# v1_0.net
KiCad netlist of a schematic drawn in EasyEDA Pro
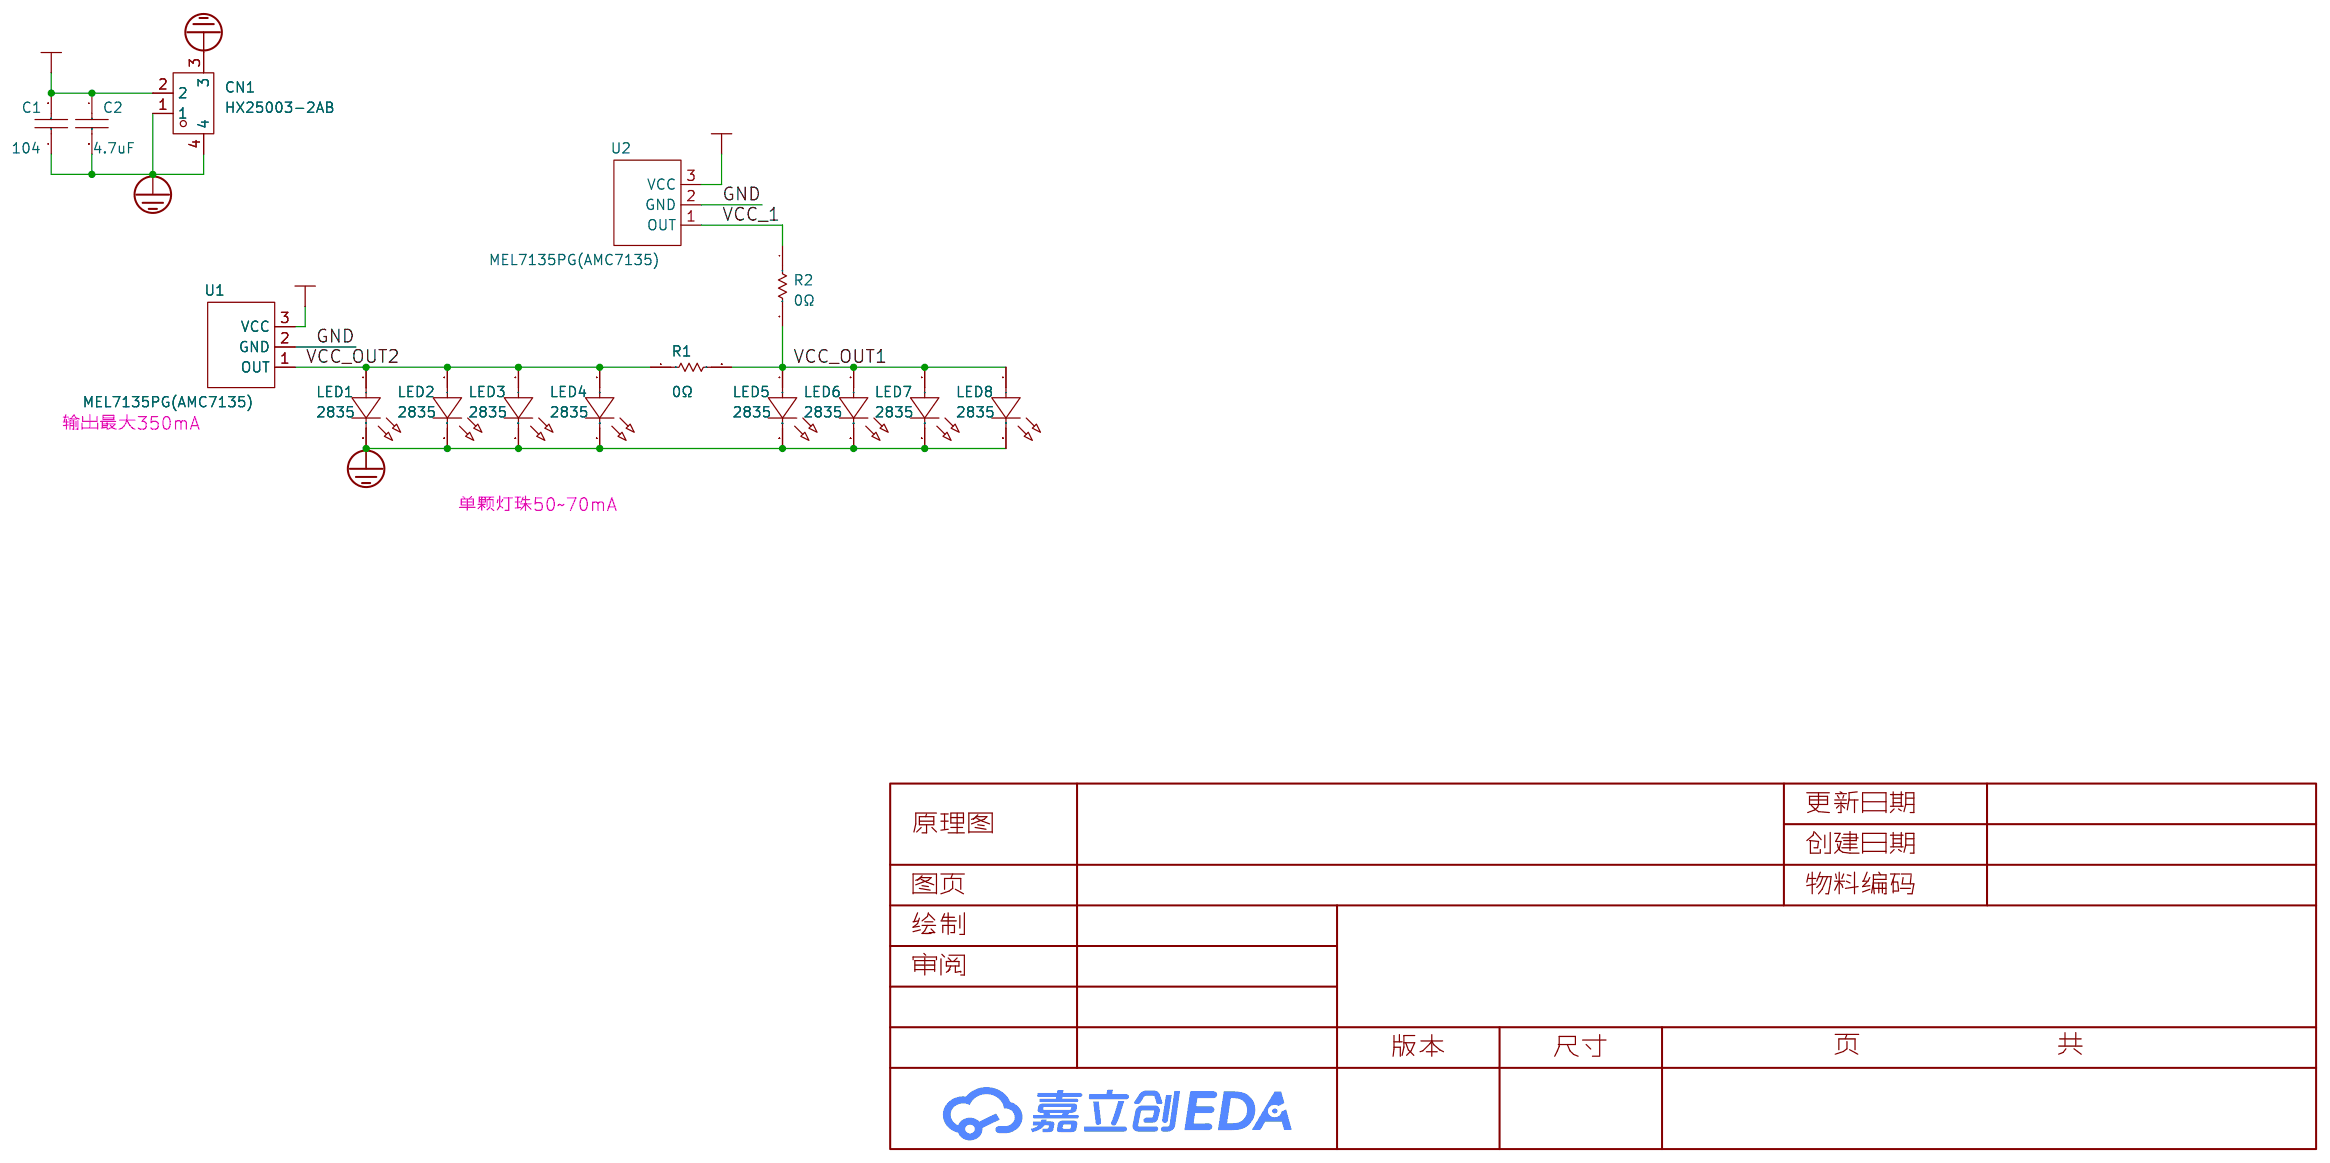
[diagram p0: schematic sheet]

(export (version "E")
  (design (tool "Eeschema 10.0.6"))
  (components
    (comp (ref "C1")
      (value "104")
      (footprint "easyedapro:0603C")
      (description "Capacitor (Semiconductor SIM Model)")
      (libsource (lib "easyedapro") (part "Cap Semi"))
    )
    (comp (ref "C2") (value "4.7uF") (libsource (lib "easyedapro") (part "CAP")))
    (comp (ref "CN1")
      (value "HX25003-2AB")
      (footprint "easyedapro:CONN-SMD_P2.50_HX25003-2AB")
      (fields (field (name "Manufacturer") "HX(红星)"))
      (libsource (lib "easyedapro") (part "HX25003-2AB"))
    )
    (comp (ref "LED1")
      (value "2835")
      (footprint "easyedapro:LED-SMD_L3.5-W2.8_2835")
      (libsource (lib "easyedapro") (part "2835"))
    )
    (comp (ref "LED2")
      (value "2835")
      (footprint "easyedapro:LED-SMD_L3.5-W2.8_2835")
      (libsource (lib "easyedapro") (part "2835"))
    )
    (comp (ref "LED3")
      (value "2835")
      (footprint "easyedapro:LED-SMD_L3.5-W2.8_2835")
      (libsource (lib "easyedapro") (part "2835"))
    )
    (comp (ref "LED4")
      (value "2835")
      (footprint "easyedapro:LED-SMD_L3.5-W2.8_2835")
      (libsource (lib "easyedapro") (part "2835"))
    )
    (comp (ref "LED5")
      (value "2835")
      (footprint "easyedapro:LED-SMD_L3.5-W2.8_2835")
      (libsource (lib "easyedapro") (part "2835"))
    )
    (comp (ref "LED6")
      (value "2835")
      (footprint "easyedapro:LED-SMD_L3.5-W2.8_2835")
      (libsource (lib "easyedapro") (part "2835"))
    )
    (comp (ref "LED7")
      (value "2835")
      (footprint "easyedapro:LED-SMD_L3.5-W2.8_2835")
      (libsource (lib "easyedapro") (part "2835"))
    )
    (comp (ref "LED8")
      (value "2835")
      (footprint "easyedapro:LED-SMD_L3.5-W2.8_2835")
      (libsource (lib "easyedapro") (part "2835"))
    )
    (comp (ref "R1")
      (value "0Ω")
      (footprint "easyedapro:10")
      (description "Resistor")
      (libsource (lib "easyedapro") (part "RES"))
    )
    (comp (ref "R2")
      (value "0Ω")
      (footprint "easyedapro:10")
      (description "Resistor")
      (libsource (lib "easyedapro") (part "RES"))
    )
    (comp (ref "U1")
      (value "MEL7135PG(AMC7135)")
      (footprint "easyedapro:SOT-89-3_L4.5-W2.5-P1.50-LS4.2-BR")
      (description "类型:-;工作电压(DC):2.7V~6V;开关频率:-;通道数:1;输出电压:-;输出电流:350mA;调光:-;拓扑结构:-;")
      (fields (field (name "Manufacturer") "MICRONE(南京微盟)"))
      (libsource (lib "easyedapro") (part "MEL7135PG"))
    )
    (comp (ref "U2")
      (value "MEL7135PG(AMC7135)")
      (footprint "easyedapro:SOT-89-3_L4.5-W2.5-P1.50-LS4.2-BR")
      (description "类型:-;工作电压(DC):2.7V~6V;开关频率:-;通道数:1;输出电压:-;输出电流:350mA;调光:-;拓扑结构:-;")
      (fields (field (name "Manufacturer") "MICRONE(南京微盟)"))
      (libsource (lib "easyedapro") (part "MEL7135PG"))
    )
  )
  (nets
    (net (code "1") (name "/VCC_1") (class "Default")
      (node (ref "R2") (pin "1") (pinfunction "1_1") (pintype "unspecified"))
      (node (ref "U2") (pin "1") (pinfunction "OUT_1") (pintype "unspecified"))
    )
    (net (code "2") (name "/VCC_OUT1") (class "Default")
      (node (ref "LED5") (pin "1") (pinfunction "A_1") (pintype "unspecified"))
      (node (ref "LED6") (pin "1") (pinfunction "A_1") (pintype "unspecified"))
      (node (ref "LED7") (pin "1") (pinfunction "A_1") (pintype "unspecified"))
      (node (ref "LED8") (pin "1") (pinfunction "A_1") (pintype "unspecified"))
      (node (ref "R1") (pin "2") (pinfunction "2_2") (pintype "unspecified"))
      (node (ref "R2") (pin "2") (pinfunction "2_2") (pintype "unspecified"))
    )
    (net (code "3") (name "/VCC_OUT2") (class "Default")
      (node (ref "LED1") (pin "1") (pinfunction "A_1") (pintype "unspecified"))
      (node (ref "LED2") (pin "1") (pinfunction "A_1") (pintype "unspecified"))
      (node (ref "LED3") (pin "1") (pinfunction "A_1") (pintype "unspecified"))
      (node (ref "LED4") (pin "1") (pinfunction "A_1") (pintype "unspecified"))
      (node (ref "R1") (pin "1") (pinfunction "1_1") (pintype "unspecified"))
      (node (ref "U1") (pin "1") (pinfunction "OUT_1") (pintype "unspecified"))
    )
    (net (code "4") (name "5V_VCC") (class "Default")
      (node (ref "C1") (pin "2") (pinfunction "2_2") (pintype "unspecified"))
      (node (ref "C2") (pin "1") (pinfunction "1_1") (pintype "input"))
      (node (ref "CN1") (pin "2") (pinfunction "2_2") (pintype "unspecified"))
      (node (ref "U1") (pin "3") (pinfunction "VCC_3") (pintype "unspecified"))
      (node (ref "U2") (pin "3") (pinfunction "VCC_3") (pintype "unspecified"))
    )
    (net (code "5") (name "GND") (class "Default")
      (node (ref "C1") (pin "1") (pinfunction "1_1") (pintype "unspecified"))
      (node (ref "C2") (pin "2") (pinfunction "2_2") (pintype "input"))
      (node (ref "CN1") (pin "1") (pinfunction "1_1") (pintype "unspecified"))
      (node (ref "CN1") (pin "3") (pinfunction "3_3") (pintype "unspecified"))
      (node (ref "CN1") (pin "4") (pinfunction "4_4") (pintype "unspecified"))
      (node (ref "LED1") (pin "2") (pinfunction "C_2") (pintype "unspecified"))
      (node (ref "LED2") (pin "2") (pinfunction "C_2") (pintype "unspecified"))
      (node (ref "LED3") (pin "2") (pinfunction "C_2") (pintype "unspecified"))
      (node (ref "LED4") (pin "2") (pinfunction "C_2") (pintype "unspecified"))
      (node (ref "LED5") (pin "2") (pinfunction "C_2") (pintype "unspecified"))
      (node (ref "LED6") (pin "2") (pinfunction "C_2") (pintype "unspecified"))
      (node (ref "LED7") (pin "2") (pinfunction "C_2") (pintype "unspecified"))
      (node (ref "LED8") (pin "2") (pinfunction "C_2") (pintype "unspecified"))
      (node (ref "U1") (pin "2") (pinfunction "GND_2") (pintype "unspecified"))
      (node (ref "U2") (pin "2") (pinfunction "GND_2") (pintype "unspecified"))
    )
  )
)
